# Knob.net
KiCad netlist of a schematic drawn in EAGLE
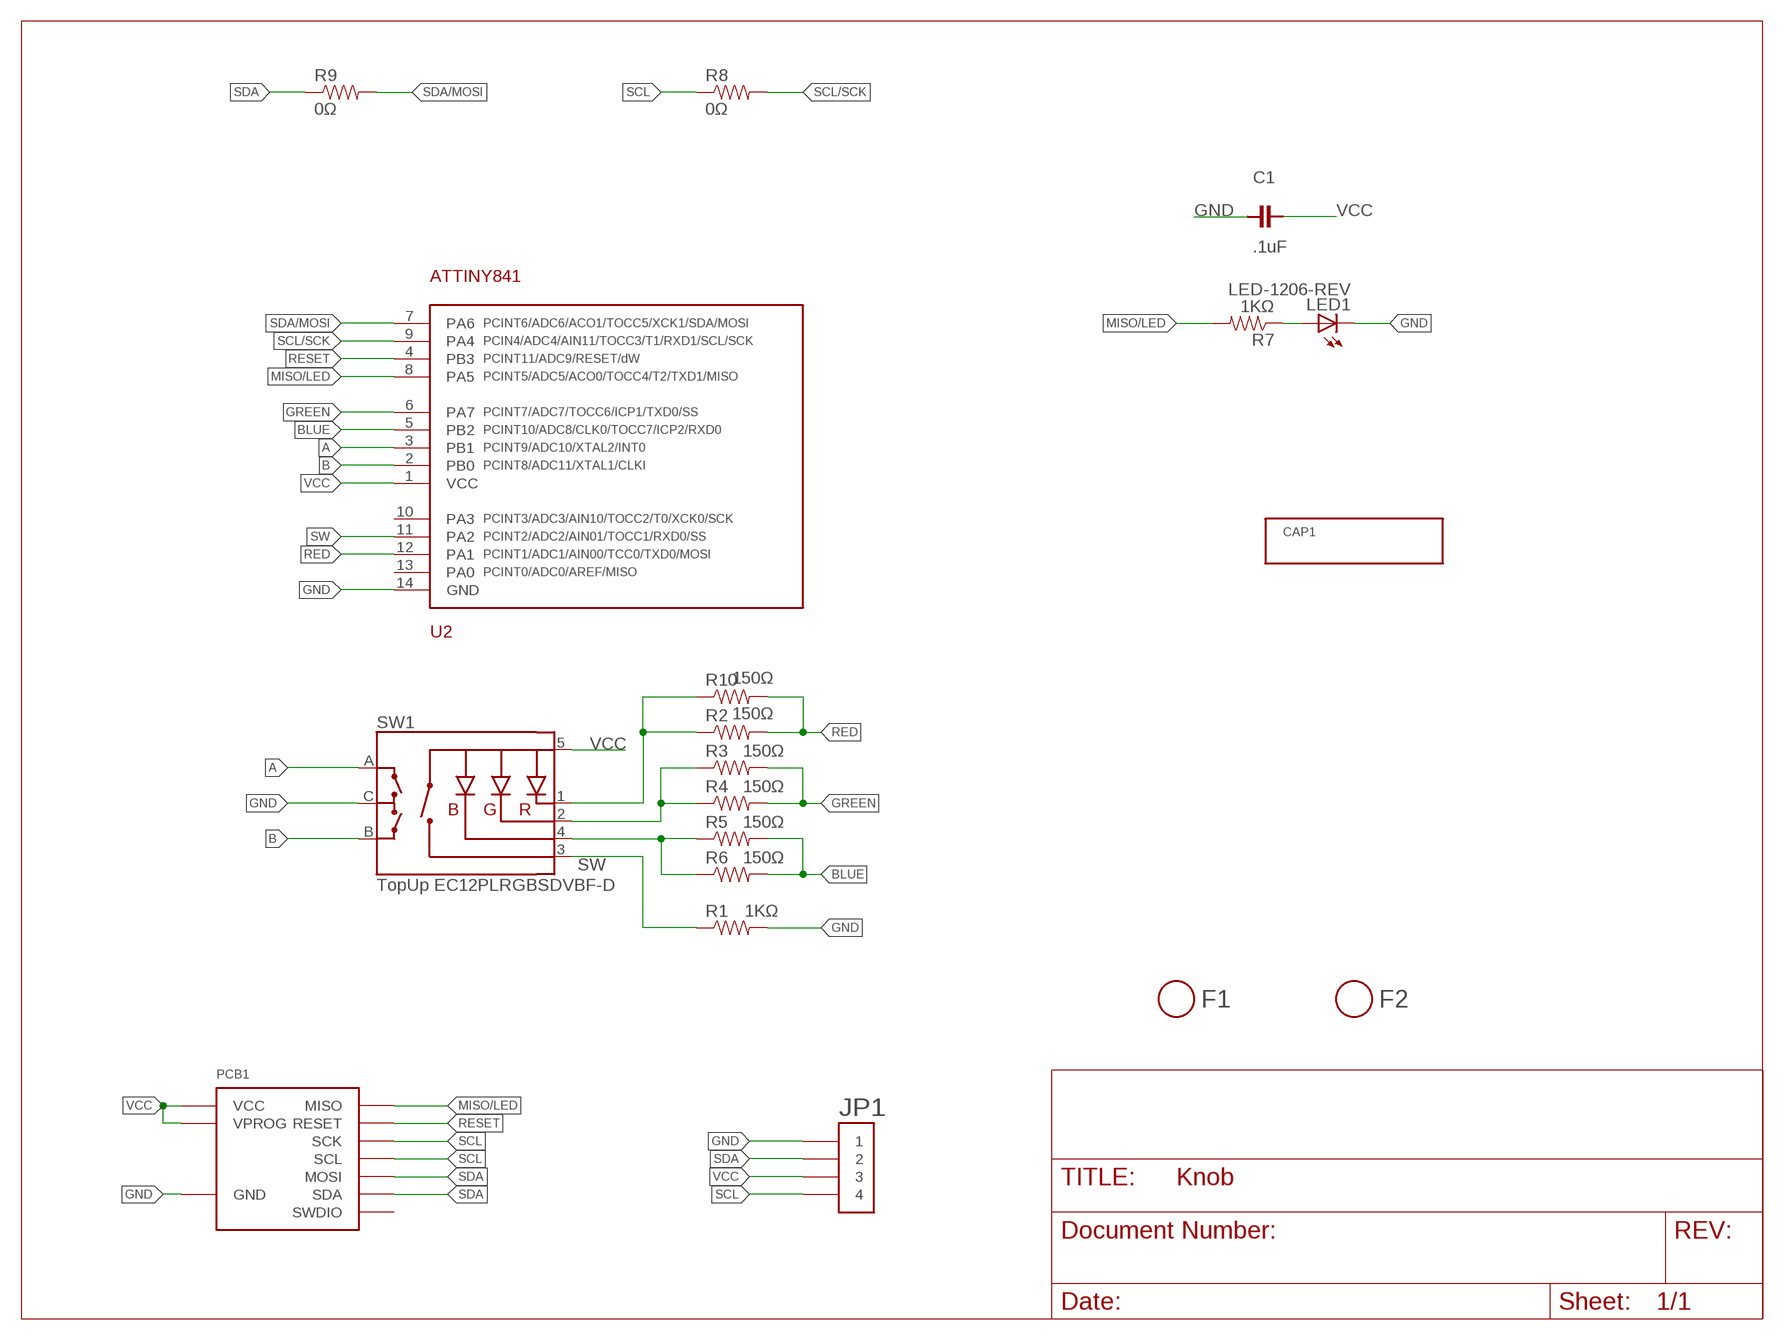
[diagram p0: schematic, sheet 1]

(export (version "E")
  (design (tool "Eeschema 10.0.6"))
  (components
    (comp (ref "C1")
      (value ".1uF")
      (footprint "eagle-import:0603")
      (fields (field (name "PARTNUM") "C0603C104K5RACTU"))
      (libsource (lib "eagle-import") (part "CAPACITOR-.1UF"))
    )
    (comp (ref "F1")
      (value "FIDUCIAL")
      (footprint "eagle-import:FIDUCIAL_1MM")
      (libsource (lib "eagle-import") (part "FIDUCIAL"))
    )
    (comp (ref "F2")
      (value "FIDUCIAL")
      (footprint "eagle-import:FIDUCIAL_1MM")
      (libsource (lib "eagle-import") (part "FIDUCIAL"))
    )
    (comp (ref "JP1")
      (value "HEADER-1X4-AMPMODU")
      (footprint "eagle-import:AMPMODU-4P")
      (fields (field (name "PARTNUM") "147721-3"))
      (libsource (lib "eagle-import") (part "HEADER-1X4-AMPMODU"))
    )
    (comp (ref "LED1")
      (value "LED-1206-REV")
      (footprint "eagle-import:LED-1206-REV")
      (fields (field (name "PARTNUM") "LTST-C230TBKT"))
      (libsource (lib "eagle-import") (part "LED-1206-REV"))
    )
    (comp (ref "PCB1")
      (value "DEVICE-PCB")
      (footprint "eagle-import:DEVICE-PCB")
      (fields (field (name "PARTNUM") "Knob PCB"))
      (libsource (lib "eagle-import") (part "DEVICE-PCB"))
    )
    (comp (ref "R1")
      (value "1KΩ")
      (footprint "eagle-import:0603")
      (fields (field (name "PARTNUM") "ERJ-3EKF1001V"))
      (libsource (lib "eagle-import") (part "RESISTOR-1KΩ"))
    )
    (comp (ref "R2")
      (value "150Ω")
      (footprint "eagle-import:0603")
      (fields (field (name "PARTNUM") "ERJ-3EKF1500V"))
      (libsource (lib "eagle-import") (part "RESISTOR-150Ω"))
    )
    (comp (ref "R3")
      (value "150Ω")
      (footprint "eagle-import:0603")
      (fields (field (name "PARTNUM") "ERJ-3EKF1500V"))
      (libsource (lib "eagle-import") (part "RESISTOR-150Ω"))
    )
    (comp (ref "R4")
      (value "150Ω")
      (footprint "eagle-import:0603")
      (fields (field (name "PARTNUM") "ERJ-3EKF1500V"))
      (libsource (lib "eagle-import") (part "RESISTOR-150Ω"))
    )
    (comp (ref "R5")
      (value "150Ω")
      (footprint "eagle-import:0603")
      (fields (field (name "PARTNUM") "ERJ-3EKF1500V"))
      (libsource (lib "eagle-import") (part "RESISTOR-150Ω"))
    )
    (comp (ref "R6")
      (value "150Ω")
      (footprint "eagle-import:0603")
      (fields (field (name "PARTNUM") "ERJ-3EKF1500V"))
      (libsource (lib "eagle-import") (part "RESISTOR-150Ω"))
    )
    (comp (ref "R7")
      (value "1KΩ")
      (footprint "eagle-import:0603")
      (fields (field (name "PARTNUM") "ERJ-3EKF1001V"))
      (libsource (lib "eagle-import") (part "RESISTOR-1KΩ"))
    )
    (comp (ref "R8")
      (value "0Ω")
      (footprint "eagle-import:0603")
      (fields (field (name "PARTNUM") "ERJ-3GEY0R00V"))
      (libsource (lib "eagle-import") (part "RESISTOR-0Ω"))
    )
    (comp (ref "R9")
      (value "0Ω")
      (footprint "eagle-import:0603")
      (fields (field (name "PARTNUM") "ERJ-3GEY0R00V"))
      (libsource (lib "eagle-import") (part "RESISTOR-0Ω"))
    )
    (comp (ref "R10")
      (value "150Ω")
      (footprint "eagle-import:0603")
      (fields (field (name "PARTNUM") "ERJ-3EKF1500V"))
      (libsource (lib "eagle-import") (part "RESISTOR-150Ω"))
    )
    (comp (ref "SW1")
      (value "TopUp EC12PLRGBSDVBF-D")
      (footprint "eagle-import:ENCODER_LED_3_SIDEPADS")
      (libsource (lib "eagle-import") (part "ENCODER_RGB_CASIDEPADS"))
    )
    (comp (ref "U2")
      (value "ATTINY841")
      (footprint "eagle-import:SOIC-14")
      (fields (field (name "PARTNUM") "ATTINY841-SSUR"))
      (libsource (lib "eagle-import") (part "ATTINY841"))
    )
  )
  (nets
    (net (code "1") (name "A") (class "Default")
      (node (ref "SW1") (pin "A") (pinfunction "A_A") (pintype "bidirectional"))
      (node (ref "U2") (pin "3") (pinfunction "PB1_3") (pintype "bidirectional"))
    )
    (net (code "2") (name "B") (class "Default")
      (node (ref "SW1") (pin "B") (pinfunction "B_B") (pintype "bidirectional"))
      (node (ref "U2") (pin "2") (pinfunction "PB0_2") (pintype "bidirectional"))
    )
    (net (code "3") (name "BLUE") (class "Default")
      (node (ref "R5") (pin "2") (pinfunction "2_2") (pintype "passive"))
      (node (ref "R6") (pin "2") (pinfunction "2_2") (pintype "passive"))
      (node (ref "U2") (pin "5") (pinfunction "PB2_5") (pintype "bidirectional"))
    )
    (net (code "4") (name "GND") (class "Default")
      (node (ref "C1") (pin "2") (pinfunction "2_2") (pintype "passive"))
      (node (ref "JP1") (pin "P$1") (pinfunction "1_P$1") (pintype "bidirectional"))
      (node (ref "JP1") (pin "P$2") (pinfunction "1_P$2") (pintype "bidirectional"))
      (node (ref "LED1") (pin "C") (pinfunction "C_C") (pintype "passive"))
      (node (ref "PCB1") (pin "GND") (pinfunction "GND_GND") (pintype "bidirectional"))
      (node (ref "R1") (pin "2") (pinfunction "2_2") (pintype "passive"))
      (node (ref "SW1") (pin "C") (pinfunction "C_C") (pintype "bidirectional"))
      (node (ref "U2") (pin "14") (pinfunction "GND_14") (pintype "bidirectional"))
    )
    (net (code "5") (name "GREEN") (class "Default")
      (node (ref "R3") (pin "2") (pinfunction "2_2") (pintype "passive"))
      (node (ref "R4") (pin "2") (pinfunction "2_2") (pintype "passive"))
      (node (ref "U2") (pin "6") (pinfunction "PA7_6") (pintype "bidirectional"))
    )
    (net (code "6") (name "MISO{slash}LED") (class "Default")
      (node (ref "PCB1") (pin "MISO") (pinfunction "MISO_MISO") (pintype "bidirectional"))
      (node (ref "R7") (pin "2") (pinfunction "2_2") (pintype "passive"))
      (node (ref "U2") (pin "8") (pinfunction "PA5_8") (pintype "bidirectional"))
    )
    (net (code "7") (name "Net-(LED1-PadA)") (class "Default")
      (node (ref "LED1") (pin "A") (pinfunction "A_A") (pintype "passive"))
      (node (ref "R7") (pin "1") (pinfunction "1_1") (pintype "passive"))
    )
    (net (code "8") (name "Net-(SW1--B)") (class "Default")
      (node (ref "R5") (pin "1") (pinfunction "1_1") (pintype "passive"))
      (node (ref "R6") (pin "1") (pinfunction "1_1") (pintype "passive"))
      (node (ref "SW1") (pin "4") (pinfunction "-B_4") (pintype "passive"))
    )
    (net (code "9") (name "Net-(SW1--G)") (class "Default")
      (node (ref "R3") (pin "1") (pinfunction "1_1") (pintype "passive"))
      (node (ref "R4") (pin "1") (pinfunction "1_1") (pintype "passive"))
      (node (ref "SW1") (pin "2") (pinfunction "-G_2") (pintype "passive"))
    )
    (net (code "10") (name "Net-(SW1--R)") (class "Default")
      (node (ref "R10") (pin "1") (pinfunction "1_1") (pintype "passive"))
      (node (ref "R2") (pin "1") (pinfunction "1_1") (pintype "passive"))
      (node (ref "SW1") (pin "1") (pinfunction "-R_1") (pintype "passive"))
    )
    (net (code "11") (name "RED") (class "Default")
      (node (ref "R10") (pin "2") (pinfunction "2_2") (pintype "passive"))
      (node (ref "R2") (pin "2") (pinfunction "2_2") (pintype "passive"))
      (node (ref "U2") (pin "12") (pinfunction "PA1_12") (pintype "bidirectional"))
    )
    (net (code "12") (name "RESET") (class "Default")
      (node (ref "PCB1") (pin "RESET") (pinfunction "RESET_RESET") (pintype "bidirectional"))
      (node (ref "U2") (pin "4") (pinfunction "PB3_4") (pintype "bidirectional"))
    )
    (net (code "13") (name "SCL") (class "Default")
      (node (ref "JP1") (pin "P$7") (pinfunction "4_P$7") (pintype "bidirectional"))
      (node (ref "JP1") (pin "P$8") (pinfunction "4_P$8") (pintype "bidirectional"))
      (node (ref "PCB1") (pin "CLK") (pinfunction "SCK_CLK") (pintype "bidirectional"))
      (node (ref "PCB1") (pin "SCL") (pinfunction "SCL_SCL") (pintype "bidirectional"))
      (node (ref "R8") (pin "1") (pinfunction "1_1") (pintype "passive"))
    )
    (net (code "14") (name "SCL{slash}SCK") (class "Default")
      (node (ref "R8") (pin "2") (pinfunction "2_2") (pintype "passive"))
      (node (ref "U2") (pin "9") (pinfunction "PA4_9") (pintype "bidirectional"))
    )
    (net (code "15") (name "SDA") (class "Default")
      (node (ref "JP1") (pin "P$3") (pinfunction "2_P$3") (pintype "bidirectional"))
      (node (ref "JP1") (pin "P$4") (pinfunction "2_P$4") (pintype "bidirectional"))
      (node (ref "PCB1") (pin "MOSI") (pinfunction "MOSI_MOSI") (pintype "bidirectional"))
      (node (ref "PCB1") (pin "SDA") (pinfunction "SDA_SDA") (pintype "bidirectional"))
      (node (ref "R9") (pin "1") (pinfunction "1_1") (pintype "passive"))
    )
    (net (code "16") (name "SDA{slash}MOSI") (class "Default")
      (node (ref "R9") (pin "2") (pinfunction "2_2") (pintype "passive"))
      (node (ref "U2") (pin "7") (pinfunction "PA6_7") (pintype "bidirectional"))
    )
    (net (code "17") (name "SW") (class "Default")
      (node (ref "R1") (pin "1") (pinfunction "1_1") (pintype "passive"))
      (node (ref "SW1") (pin "3") (pinfunction "SW_3") (pintype "passive"))
      (node (ref "U2") (pin "11") (pinfunction "PA2_11") (pintype "bidirectional"))
    )
    (net (code "18") (name "VCC") (class "Default")
      (node (ref "C1") (pin "1") (pinfunction "1_1") (pintype "passive"))
      (node (ref "JP1") (pin "P$5") (pinfunction "3_P$5") (pintype "bidirectional"))
      (node (ref "JP1") (pin "P$6") (pinfunction "3_P$6") (pintype "bidirectional"))
      (node (ref "PCB1") (pin "VCC") (pinfunction "VCC_VCC") (pintype "bidirectional"))
      (node (ref "PCB1") (pin "VPROG") (pinfunction "VPROG_VPROG") (pintype "bidirectional"))
      (node (ref "SW1") (pin "5") (pinfunction "+_5") (pintype "passive"))
      (node (ref "U2") (pin "1") (pinfunction "VCC_1") (pintype "bidirectional"))
    )
    (net (code "19") (name "unconnected-(PCB1-PadSWDIO)") (class "Default")
      (node (ref "PCB1") (pin "SWDIO") (pinfunction "SWDIO_SWDIO") (pintype "bidirectional"))
    )
    (net (code "20") (name "unconnected-(U2-PA0-Pad13)") (class "Default")
      (node (ref "U2") (pin "13") (pinfunction "PA0_13") (pintype "bidirectional"))
    )
    (net (code "21") (name "unconnected-(U2-PA3-Pad10)") (class "Default")
      (node (ref "U2") (pin "10") (pinfunction "PA3_10") (pintype "bidirectional"))
    )
  )
)
